# Schematic_Tree_keychain.net
KiCad netlist of a schematic drawn in EasyEDA
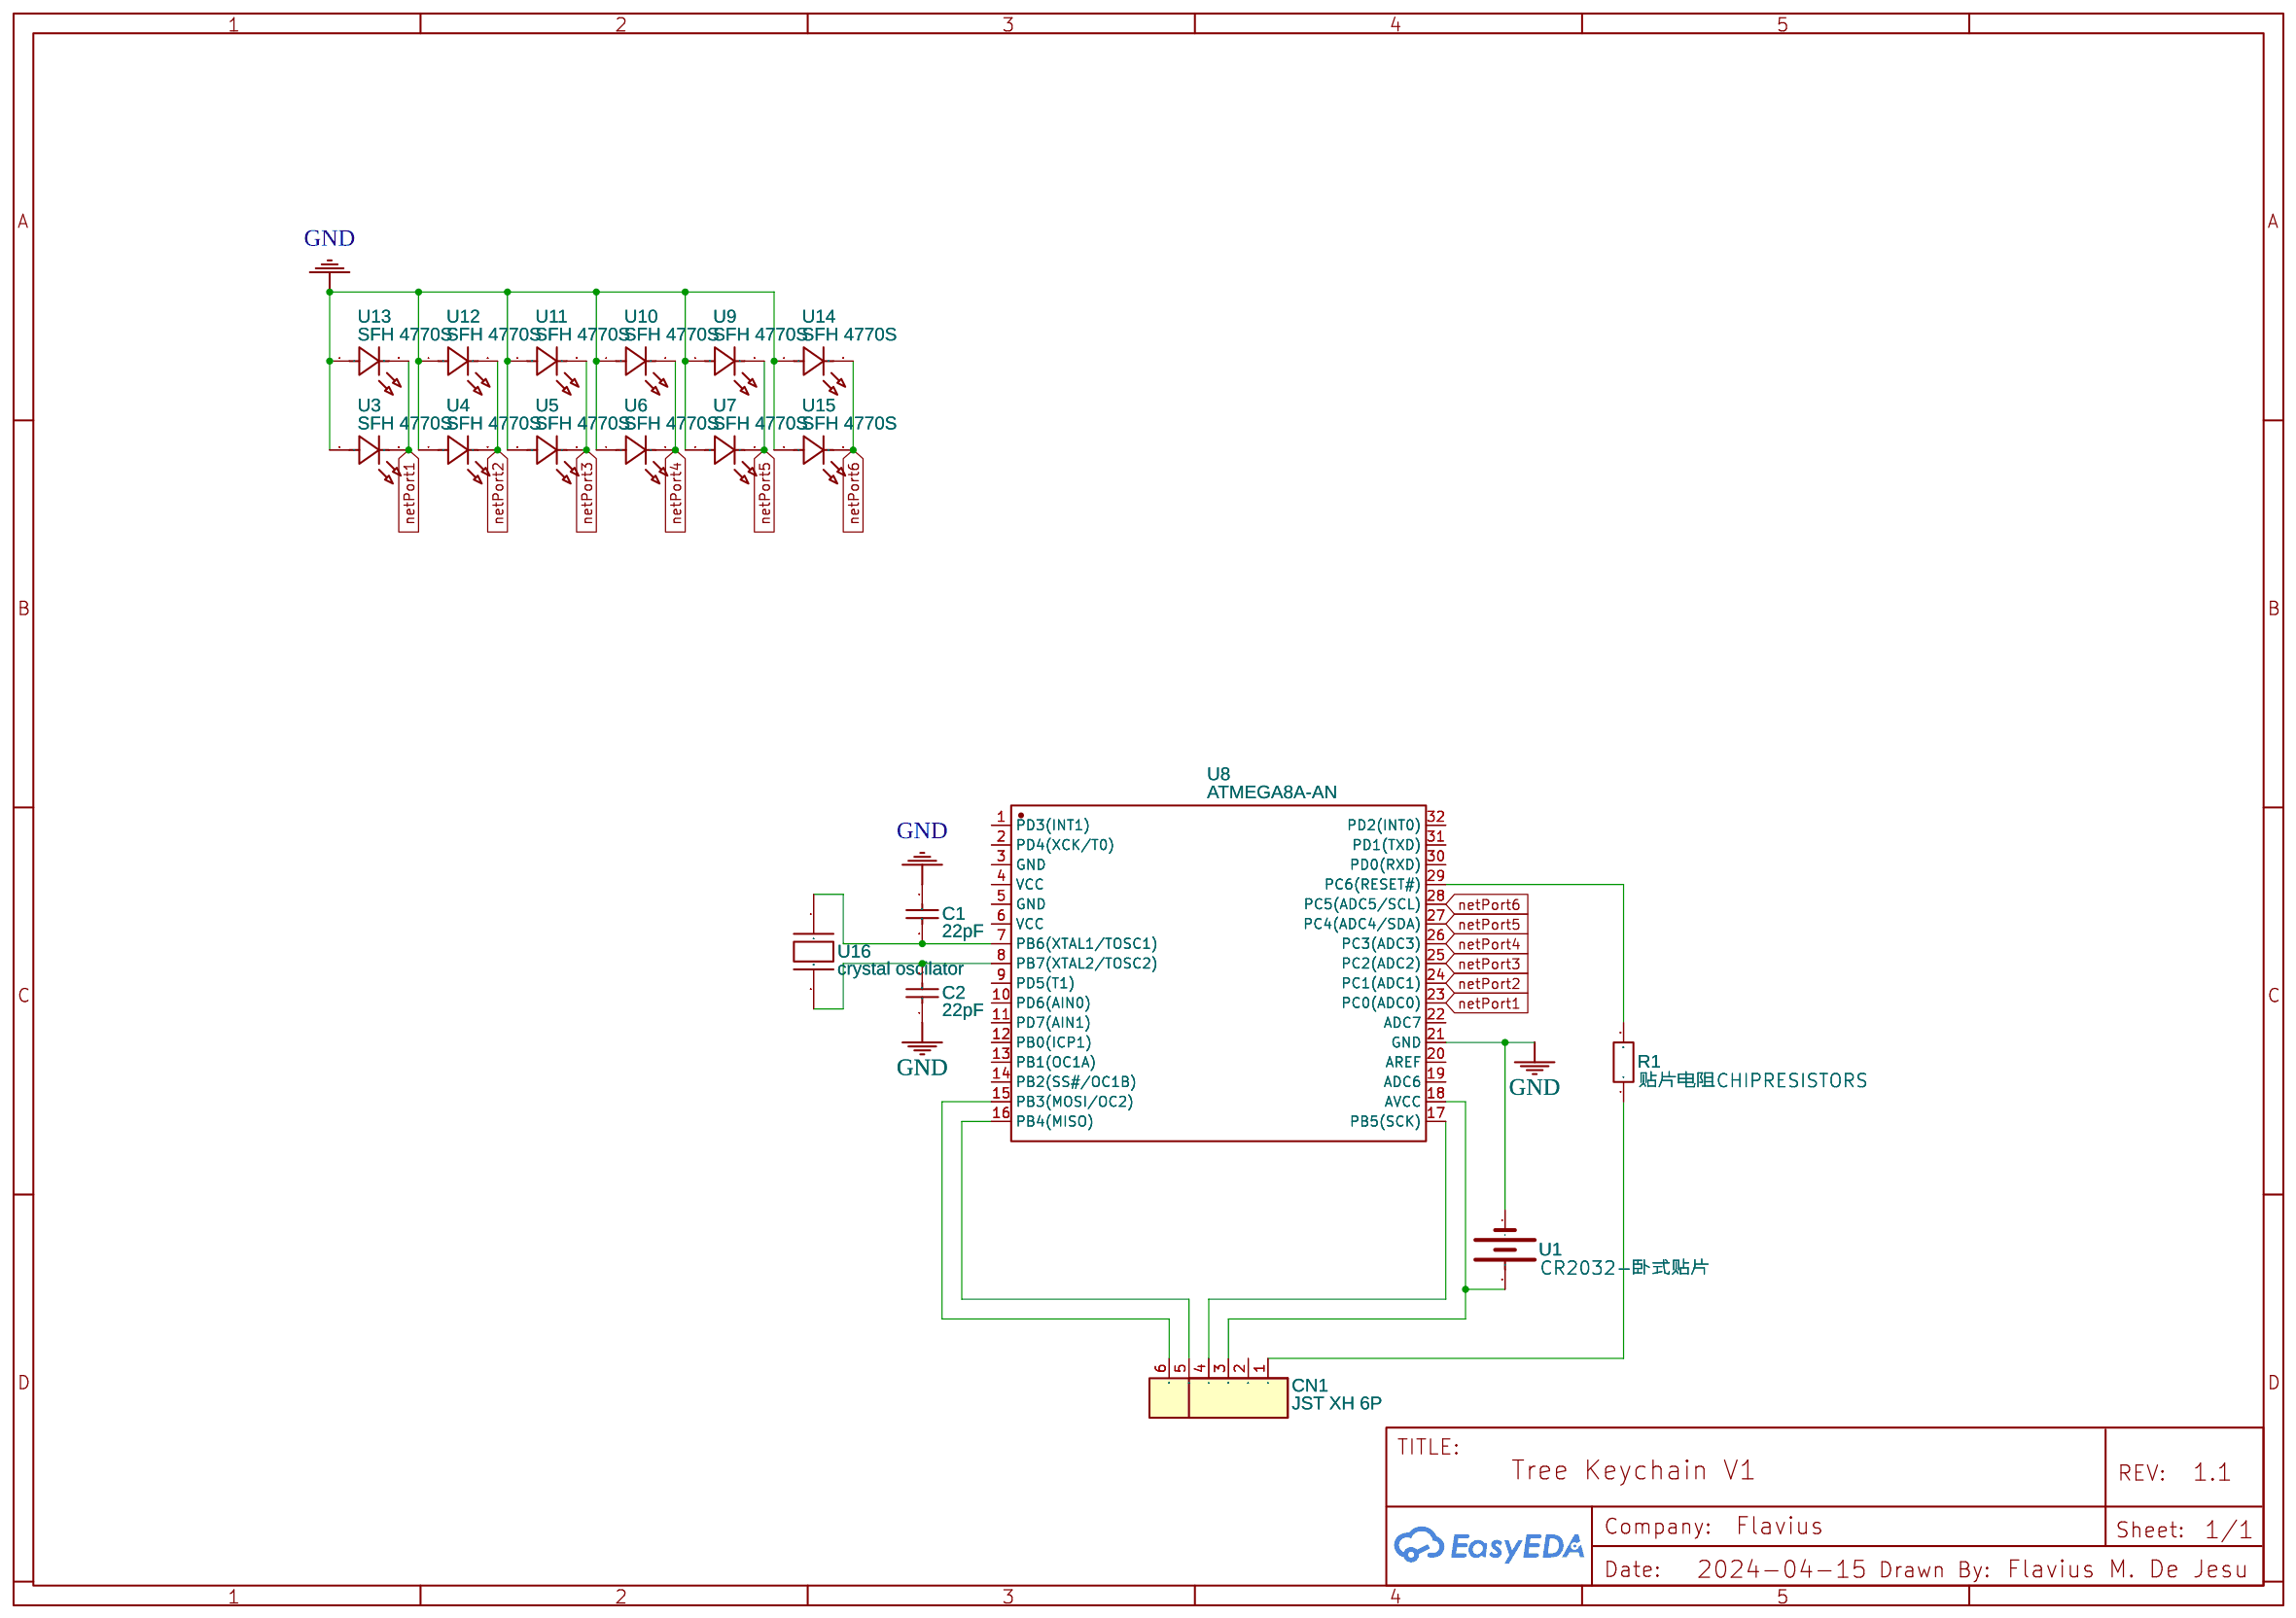
[diagram p0: schematic sheet]

(export (version "E")
  (design (tool "Eeschema 10.0.6"))
  (components
    (comp (ref "C1")
      (value "22pF")
      (fields (field (name "Manufacturer Part") "22pf/50V 10%") (field (name "Manufacturer") "ReliaPro"))
      (libsource (lib "") (part "22pf/50V 10%_1"))
    )
    (comp (ref "C2")
      (value "22pF")
      (fields (field (name "Manufacturer Part") "22pf/50V 10%") (field (name "Manufacturer") "ReliaPro"))
      (libsource (lib "") (part "22pf/50V 10%"))
    )
    (comp (ref "CN1") (value "JST XH 6P") (libsource (lib "") (part "JST XH 6P")))
    (comp (ref "R1")
      (value "贴片电阻CHIPRESISTORS")
      (fields (field (name "Manufacturer Part") "贴片电阻ChipResistors"))
      (libsource (lib "") (part "贴片电阻CHIPRESISTORS"))
    )
    (comp (ref "U1") (value "CR2032-卧式贴片") (libsource (lib "") (part "CR2032-卧式贴片")))
    (comp (ref "U3")
      (value "SFH 4770S")
      (fields (field (name "Manufacturer") "OSRAM(欧司朗)"))
      (libsource (lib "") (part "SFH 4770S"))
    )
    (comp (ref "U4")
      (value "SFH 4770S")
      (fields (field (name "Manufacturer") "OSRAM(欧司朗)"))
      (libsource (lib "") (part "SFH 4770S"))
    )
    (comp (ref "U5")
      (value "SFH 4770S")
      (fields (field (name "Manufacturer") "OSRAM(欧司朗)"))
      (libsource (lib "") (part "SFH 4770S"))
    )
    (comp (ref "U6")
      (value "SFH 4770S")
      (fields (field (name "Manufacturer") "OSRAM(欧司朗)"))
      (libsource (lib "") (part "SFH 4770S"))
    )
    (comp (ref "U7")
      (value "SFH 4770S")
      (fields (field (name "Manufacturer") "OSRAM(欧司朗)"))
      (libsource (lib "") (part "SFH 4770S"))
    )
    (comp (ref "U8")
      (value "ATMEGA8A-AN")
      (fields (field (name "Manufacturer") "MICROCHIP(美国微芯)"))
      (libsource (lib "") (part "ATMEGA8A-AN"))
    )
    (comp (ref "U9")
      (value "SFH 4770S")
      (fields (field (name "Manufacturer") "OSRAM(欧司朗)"))
      (libsource (lib "") (part "SFH 4770S"))
    )
    (comp (ref "U10")
      (value "SFH 4770S")
      (fields (field (name "Manufacturer") "OSRAM(欧司朗)"))
      (libsource (lib "") (part "SFH 4770S"))
    )
    (comp (ref "U11")
      (value "SFH 4770S")
      (fields (field (name "Manufacturer") "OSRAM(欧司朗)"))
      (libsource (lib "") (part "SFH 4770S"))
    )
    (comp (ref "U12")
      (value "SFH 4770S")
      (fields (field (name "Manufacturer") "OSRAM(欧司朗)"))
      (libsource (lib "") (part "SFH 4770S"))
    )
    (comp (ref "U13")
      (value "SFH 4770S")
      (fields (field (name "Manufacturer") "OSRAM(欧司朗)"))
      (libsource (lib "") (part "SFH 4770S"))
    )
    (comp (ref "U14")
      (value "SFH 4770S")
      (fields (field (name "Manufacturer") "OSRAM(欧司朗)"))
      (libsource (lib "") (part "SFH 4770S"))
    )
    (comp (ref "U15")
      (value "SFH 4770S")
      (fields (field (name "Manufacturer") "OSRAM(欧司朗)"))
      (libsource (lib "") (part "SFH 4770S"))
    )
    (comp (ref "U16") (value "crystal oscilator") (libsource (lib "") (part "crystal oscilator")))
  )
  (nets
    (net (code "1") (name "GND") (class "Default")
      (node (ref "C1") (pin "1") (pinfunction "1_1") (pintype "input"))
      (node (ref "C2") (pin "1") (pinfunction "1_1") (pintype "input"))
      (node (ref "U1") (pin "1") (pinfunction "-_1") (pintype "passive"))
      (node (ref "U10") (pin "1") (pinfunction "A_1") (pintype "unspecified"))
      (node (ref "U11") (pin "1") (pinfunction "A_1") (pintype "unspecified"))
      (node (ref "U12") (pin "1") (pinfunction "A_1") (pintype "unspecified"))
      (node (ref "U13") (pin "1") (pinfunction "A_1") (pintype "unspecified"))
      (node (ref "U14") (pin "1") (pinfunction "A_1") (pintype "unspecified"))
      (node (ref "U15") (pin "1") (pinfunction "A_1") (pintype "unspecified"))
      (node (ref "U3") (pin "1") (pinfunction "A_1") (pintype "unspecified"))
      (node (ref "U4") (pin "1") (pinfunction "A_1") (pintype "unspecified"))
      (node (ref "U5") (pin "1") (pinfunction "A_1") (pintype "unspecified"))
      (node (ref "U6") (pin "1") (pinfunction "A_1") (pintype "unspecified"))
      (node (ref "U7") (pin "1") (pinfunction "A_1") (pintype "unspecified"))
      (node (ref "U8") (pin "21") (pinfunction "GND_21") (pintype "unspecified"))
      (node (ref "U9") (pin "1") (pinfunction "A_1") (pintype "unspecified"))
    )
    (net (code "2") (name "Net-(CN1-Pad1)") (class "Default")
      (node (ref "CN1") (pin "1") (pinfunction "1_1") (pintype "unspecified"))
      (node (ref "R1") (pin "1") (pinfunction "1_1") (pintype "unspecified"))
    )
    (net (code "3") (name "Net-(U1-+)") (class "Default")
      (node (ref "CN1") (pin "3") (pinfunction "3_3") (pintype "unspecified"))
      (node (ref "U1") (pin "2") (pinfunction "+_2") (pintype "passive"))
      (node (ref "U8") (pin "18") (pinfunction "AVCC_18") (pintype "unspecified"))
    )
    (net (code "4") (name "Net-(U8-PB3(MOSI{slash}OC2))") (class "Default")
      (node (ref "CN1") (pin "6") (pinfunction "6_6") (pintype "unspecified"))
      (node (ref "U8") (pin "15") (pinfunction "PB3(MOSI/OC2)_15") (pintype "unspecified"))
    )
    (net (code "5") (name "Net-(U8-PB4(MISO))") (class "Default")
      (node (ref "CN1") (pin "5") (pinfunction "5_5") (pintype "unspecified"))
      (node (ref "U8") (pin "16") (pinfunction "PB4(MISO)_16") (pintype "unspecified"))
    )
    (net (code "6") (name "Net-(U8-PB5(SCK))") (class "Default")
      (node (ref "CN1") (pin "4") (pinfunction "4_4") (pintype "unspecified"))
      (node (ref "U8") (pin "17") (pinfunction "PB5(SCK)_17") (pintype "unspecified"))
    )
    (net (code "7") (name "Net-(U8-PB6(XTAL1{slash}TOSC1))") (class "Default")
      (node (ref "C1") (pin "2") (pinfunction "2_2") (pintype "input"))
      (node (ref "U16") (pin "1") (pinfunction "1_1") (pintype "unspecified"))
      (node (ref "U8") (pin "7") (pinfunction "PB6(XTAL1/TOSC1)_7") (pintype "unspecified"))
    )
    (net (code "8") (name "Net-(U8-PB7(XTAL2{slash}TOSC2))") (class "Default")
      (node (ref "C2") (pin "2") (pinfunction "2_2") (pintype "input"))
      (node (ref "U16") (pin "2") (pinfunction "2_2") (pintype "unspecified"))
      (node (ref "U8") (pin "8") (pinfunction "PB7(XTAL2/TOSC2)_8") (pintype "unspecified"))
    )
    (net (code "9") (name "Net-(U8-PC6(RESET#))") (class "Default")
      (node (ref "R1") (pin "2") (pinfunction "2_2") (pintype "unspecified"))
      (node (ref "U8") (pin "29") (pinfunction "PC6(RESET#)_29") (pintype "unspecified"))
    )
    (net (code "10") (name "netPort1") (class "Default")
      (node (ref "U13") (pin "2") (pinfunction "K_2") (pintype "unspecified"))
      (node (ref "U3") (pin "2") (pinfunction "K_2") (pintype "unspecified"))
      (node (ref "U8") (pin "23") (pinfunction "PC0(ADC0)_23") (pintype "unspecified"))
    )
    (net (code "11") (name "netPort2") (class "Default")
      (node (ref "U12") (pin "2") (pinfunction "K_2") (pintype "unspecified"))
      (node (ref "U4") (pin "2") (pinfunction "K_2") (pintype "unspecified"))
      (node (ref "U8") (pin "24") (pinfunction "PC1(ADC1)_24") (pintype "unspecified"))
    )
    (net (code "12") (name "netPort3") (class "Default")
      (node (ref "U11") (pin "2") (pinfunction "K_2") (pintype "unspecified"))
      (node (ref "U5") (pin "2") (pinfunction "K_2") (pintype "unspecified"))
      (node (ref "U8") (pin "25") (pinfunction "PC2(ADC2)_25") (pintype "unspecified"))
    )
    (net (code "13") (name "netPort4") (class "Default")
      (node (ref "U10") (pin "2") (pinfunction "K_2") (pintype "unspecified"))
      (node (ref "U6") (pin "2") (pinfunction "K_2") (pintype "unspecified"))
      (node (ref "U8") (pin "26") (pinfunction "PC3(ADC3)_26") (pintype "unspecified"))
    )
    (net (code "14") (name "netPort5") (class "Default")
      (node (ref "U7") (pin "2") (pinfunction "K_2") (pintype "unspecified"))
      (node (ref "U8") (pin "27") (pinfunction "PC4(ADC4/SDA)_27") (pintype "unspecified"))
      (node (ref "U9") (pin "2") (pinfunction "K_2") (pintype "unspecified"))
    )
    (net (code "15") (name "netPort6") (class "Default")
      (node (ref "U14") (pin "2") (pinfunction "K_2") (pintype "unspecified"))
      (node (ref "U15") (pin "2") (pinfunction "K_2") (pintype "unspecified"))
      (node (ref "U8") (pin "28") (pinfunction "PC5(ADC5/SCL)_28") (pintype "unspecified"))
    )
    (net (code "16") (name "unconnected-(CN1-Pad2)") (class "Default")
      (node (ref "CN1") (pin "2") (pinfunction "2_2") (pintype "unspecified"))
    )
    (net (code "17") (name "unconnected-(U8-ADC6-Pad19)") (class "Default")
      (node (ref "U8") (pin "19") (pinfunction "ADC6_19") (pintype "unspecified"))
    )
    (net (code "18") (name "unconnected-(U8-ADC7-Pad22)") (class "Default")
      (node (ref "U8") (pin "22") (pinfunction "ADC7_22") (pintype "unspecified"))
    )
    (net (code "19") (name "unconnected-(U8-AREF-Pad20)") (class "Default")
      (node (ref "U8") (pin "20") (pinfunction "AREF_20") (pintype "unspecified"))
    )
    (net (code "20") (name "unconnected-(U8-GND-Pad3)") (class "Default")
      (node (ref "U8") (pin "3") (pinfunction "GND_3") (pintype "unspecified"))
    )
    (net (code "21") (name "unconnected-(U8-GND-Pad5)") (class "Default")
      (node (ref "U8") (pin "5") (pinfunction "GND_5") (pintype "unspecified"))
    )
    (net (code "22") (name "unconnected-(U8-PB0(ICP1)-Pad12)") (class "Default")
      (node (ref "U8") (pin "12") (pinfunction "PB0(ICP1)_12") (pintype "unspecified"))
    )
    (net (code "23") (name "unconnected-(U8-PB1(OC1A)-Pad13)") (class "Default")
      (node (ref "U8") (pin "13") (pinfunction "PB1(OC1A)_13") (pintype "unspecified"))
    )
    (net (code "24") (name "unconnected-(U8-PB2(SS#{slash}OC1B)-Pad14)") (class "Default")
      (node (ref "U8") (pin "14") (pinfunction "PB2(SS#/OC1B)_14") (pintype "unspecified"))
    )
    (net (code "25") (name "unconnected-(U8-PD0(RXD)-Pad30)") (class "Default")
      (node (ref "U8") (pin "30") (pinfunction "PD0(RXD)_30") (pintype "unspecified"))
    )
    (net (code "26") (name "unconnected-(U8-PD1(TXD)-Pad31)") (class "Default")
      (node (ref "U8") (pin "31") (pinfunction "PD1(TXD)_31") (pintype "unspecified"))
    )
    (net (code "27") (name "unconnected-(U8-PD2(INT0)-Pad32)") (class "Default")
      (node (ref "U8") (pin "32") (pinfunction "PD2(INT0)_32") (pintype "unspecified"))
    )
    (net (code "28") (name "unconnected-(U8-PD3(INT1)-Pad1)") (class "Default")
      (node (ref "U8") (pin "1") (pinfunction "PD3(INT1)_1") (pintype "unspecified"))
    )
    (net (code "29") (name "unconnected-(U8-PD4(XCK{slash}T0)-Pad2)") (class "Default")
      (node (ref "U8") (pin "2") (pinfunction "PD4(XCK/T0)_2") (pintype "unspecified"))
    )
    (net (code "30") (name "unconnected-(U8-PD5(T1)-Pad9)") (class "Default")
      (node (ref "U8") (pin "9") (pinfunction "PD5(T1)_9") (pintype "unspecified"))
    )
    (net (code "31") (name "unconnected-(U8-PD6(AIN0)-Pad10)") (class "Default")
      (node (ref "U8") (pin "10") (pinfunction "PD6(AIN0)_10") (pintype "unspecified"))
    )
    (net (code "32") (name "unconnected-(U8-PD7(AIN1)-Pad11)") (class "Default")
      (node (ref "U8") (pin "11") (pinfunction "PD7(AIN1)_11") (pintype "unspecified"))
    )
    (net (code "33") (name "unconnected-(U8-VCC-Pad4)") (class "Default")
      (node (ref "U8") (pin "4") (pinfunction "VCC_4") (pintype "unspecified"))
    )
    (net (code "34") (name "unconnected-(U8-VCC-Pad6)") (class "Default")
      (node (ref "U8") (pin "6") (pinfunction "VCC_6") (pintype "unspecified"))
    )
  )
)
